# Amp_channel.net
KiCad netlist of a schematic drawn in Altium Designer
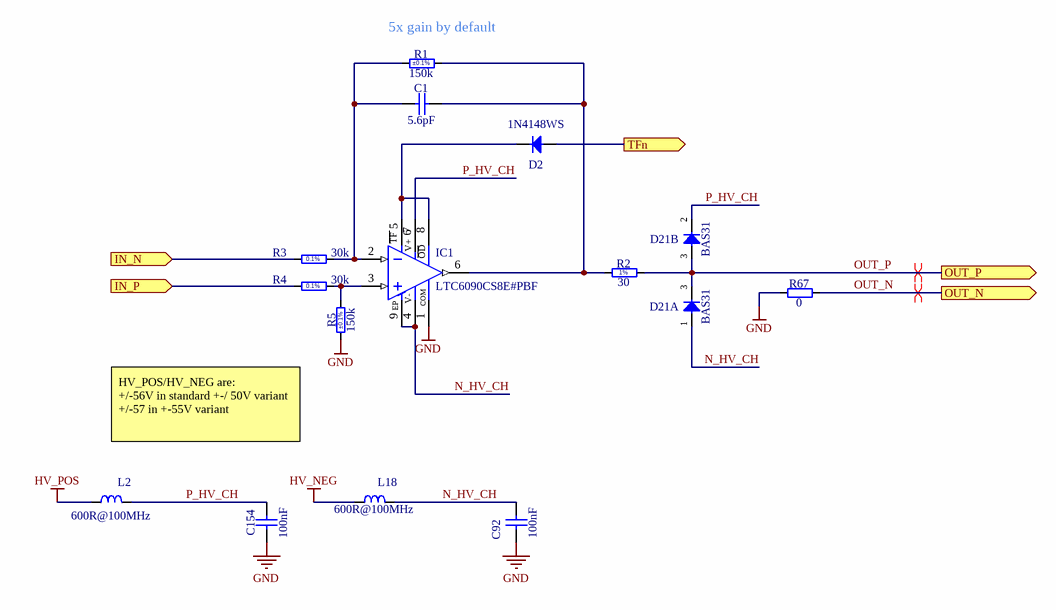
[diagram p0: Amp_channel.SchDoc]

(export (version "E")
  (design (tool "Eeschema 10.0.6"))
  (components
    (comp (ref "C1")
      (value "5.6pF")
      (footprint "CAPC1608X87N")
      (description "Non-polarised capacitor")
      (fields
        (field (name "PART NUMBER") "CC0603_5.6PF_50V_0.5PF_NP0")
        (field (name "MANUFACTURER") "GENERIC")
        (field (name "AUTHOR") "CERN DEM JLC")
      )
      (libsource (lib "Capacitors") (part "Capacitor - non polarized"))
    )
    (comp (ref "C92")
      (value "100nF")
      (footprint "CAPC1608X90N")
      (description "Non-polarised capacitor")
      (fields
        (field (name "PART NUMBER") "CC0603_100NF_100V_10%_X7R")
        (field (name "VOLTAGE") "100V")
        (field (name "AUTHOR") "CERN DEM JLC")
      )
      (libsource (lib "Capacitors") (part "Capacitor - non polarized"))
    )
    (comp (ref "C154")
      (value "100nF")
      (footprint "CAPC1608X90N")
      (description "Non-polarised capacitor")
      (fields
        (field (name "PART NUMBER") "CC0603_100NF_100V_10%_X7R")
        (field (name "VOLTAGE") "100V")
        (field (name "AUTHOR") "CERN DEM JLC")
      )
      (libsource (lib "Capacitors") (part "Capacitor - non polarized"))
    )
    (comp (ref "D2")
      (value "1N4148WS")
      (footprint "SODFL2512X100N")
      (description "Diode")
      (fields
        (field (name "VOLTAGE") "75V")
        (field (name "POWER") "150mA")
        (field (name "AUTHOR") "CERN DEM JLC")
      )
      (libsource (lib "ICs And Semiconductors") (part "Diode"))
    )
    (comp (ref "D21")
      (value "BAS31")
      (footprint "SOT95P240X130-3N")
      (description "Serial Diode")
      (fields
        (field (name "VOLTAGE") "120V")
        (field (name "POWER") "200mA")
        (field (name "AUTHOR") "CERN DEM JLC")
      )
      (libsource (lib "ICs And Semiconductors") (part "Diode x2 A1C3_A3C2"))
    )
    (comp (ref "IC1")
      (value "LTC6090CS8E#PBF")
      (footprint "SOIC127P599X175-9N-R249X350")
      (description "140V CMOS Rail-to-Rail Output, Picoamp Input Current Operational Amplifier")
      (fields (field (name "MANUFACTURER") "LINEAR TECHNOLOGY") (field (name "AUTHOR") "CERN DEM JLC"))
      (libsource (lib "ICs And Semiconductors") (part "LTC6090CS8E"))
    )
    (comp (ref "L2")
      (value "600R@100MHz")
      (footprint "INDC1005X55N")
      (description "Inductor")
      (fields
        (field (name "PART NUMBER") "IND0402_MURATA_BLM15HD601SN1")
        (field (name "POWER") "300mA")
        (field (name "AUTHOR") "CERN DEM JLC")
      )
      (libsource (lib "Inductors & Transformers") (part "Inductor"))
    )
    (comp (ref "L18")
      (value "600R@100MHz")
      (footprint "INDC1005X55N")
      (description "Inductor")
      (fields
        (field (name "PART NUMBER") "IND0402_MURATA_BLM15HD601SN1")
        (field (name "POWER") "300mA")
        (field (name "AUTHOR") "CERN DEM JLC")
      )
      (libsource (lib "Inductors & Transformers") (part "Inductor"))
    )
    (comp (ref "R1")
      (value "150k")
      (footprint "RESC1608X55N")
      (description "Resistor - 0.1%")
      (fields
        (field (name "TOLERANCE") "±0.1%")
        (field (name "PART NUMBER") "R0603_150K_0.1%_0.063W_10PPM")
        (field (name "POWER") "0.063W")
        (field (name "AUTHOR") "CERN DEM JLC")
      )
      (libsource (lib "Resistors") (part "Resistor - 0.1%"))
    )
    (comp (ref "R2")
      (value "30")
      (footprint "RESC1608X55N")
      (description "Resistor - 1%")
      (fields
        (field (name "PART NUMBER") "R0603_30R_1%_0.1W_100PPM")
        (field (name "POWER") "0.1W")
        (field (name "AUTHOR") "CERN DEM JLC")
      )
      (libsource (lib "Resistors") (part "Resistor - 1%"))
    )
    (comp (ref "R3")
      (value "30k")
      (footprint "RESC1005X40N")
      (description "Resistor - 1%")
      (fields
        (field (name "PART NUMBER") "R0603_30K0_0.1%_0.063W_10PPM")
        (field (name "POWER") "0.063W")
        (field (name "AUTHOR") "GK")
      )
      (libsource (lib "Passives_RC") (part "R0603_30K0_0.1%_0.063W_10PPM"))
    )
    (comp (ref "R4")
      (value "30k")
      (footprint "RESC1005X40N")
      (description "Resistor - 1%")
      (fields
        (field (name "PART NUMBER") "R0603_30K0_0.1%_0.063W_10PPM")
        (field (name "POWER") "0.063W")
        (field (name "AUTHOR") "GK")
      )
      (libsource (lib "Passives_RC") (part "R0603_30K0_0.1%_0.063W_10PPM"))
    )
    (comp (ref "R5")
      (value "150k")
      (footprint "RESC1608X55N")
      (description "Resistor - 0.1%")
      (fields
        (field (name "TOLERANCE") "±0.1%")
        (field (name "PART NUMBER") "R0603_150K_0.1%_0.063W_10PPM")
        (field (name "POWER") "0.063W")
        (field (name "AUTHOR") "CERN DEM JLC")
      )
      (libsource (lib "Resistors") (part "Resistor - 0.1%"))
    )
    (comp (ref "R67")
      (value "0")
      (footprint "RESC1608X55N")
      (description "Resistor")
      (fields
        (field (name "PART NUMBER") "R0603_0R_JUMPER")
        (field (name "MANUFACTURER") "GENERIC")
        (field (name "AUTHOR") "CERN DEM JLC")
      )
      (libsource (lib "Resistors") (part "Resistor"))
    )
  )
  (nets
    (net (code "1") (name "/IN_N") (class "Default")
      (node (ref "R3") (pin "1") (pinfunction "1_1") (pintype "passive"))
    )
    (net (code "2") (name "/IN_P") (class "Default")
      (node (ref "R4") (pin "1") (pinfunction "1_1") (pintype "passive"))
    )
    (net (code "3") (name "/N_HV_CH") (class "Default")
      (node (ref "C92") (pin "2") (pinfunction "2_2") (pintype "passive"))
      (node (ref "D21") (pin "1") (pinfunction "A_1") (pintype "passive"))
      (node (ref "IC1") (pin "4") (pinfunction "V-_4") (pintype "power_in"))
      (node (ref "IC1") (pin "9") (pinfunction "EP_9") (pintype "power_in"))
      (node (ref "L18") (pin "2") (pinfunction "2_2") (pintype "passive"))
    )
    (net (code "4") (name "/OUT_N") (class "Default")
      (node (ref "R67") (pin "2") (pinfunction "2_2") (pintype "passive"))
    )
    (net (code "5") (name "/OUT_P") (class "Default")
      (node (ref "D21") (pin "3") (pinfunction "COMAC_3") (pintype "passive"))
      (node (ref "R2") (pin "2") (pinfunction "2_2") (pintype "passive"))
    )
    (net (code "6") (name "/P_HV_CH") (class "Default")
      (node (ref "C154") (pin "2") (pinfunction "2_2") (pintype "passive"))
      (node (ref "D21") (pin "2") (pinfunction "C_2") (pintype "passive"))
      (node (ref "IC1") (pin "7") (pinfunction "V+_7") (pintype "power_in"))
      (node (ref "L2") (pin "2") (pinfunction "2_2") (pintype "passive"))
    )
    (net (code "7") (name "/TFn") (class "Default")
      (node (ref "D2") (pin "2") (pinfunction "A_2") (pintype "passive"))
    )
    (net (code "8") (name "GND") (class "Default")
      (node (ref "C154") (pin "1") (pinfunction "1_1") (pintype "passive"))
      (node (ref "C92") (pin "1") (pinfunction "1_1") (pintype "passive"))
      (node (ref "IC1") (pin "1") (pinfunction "COM_1") (pintype "power_in"))
      (node (ref "R5") (pin "1") (pinfunction "1_1") (pintype "passive"))
      (node (ref "R67") (pin "1") (pinfunction "1_1") (pintype "passive"))
    )
    (net (code "9") (name "HV_NEG") (class "Default")
      (node (ref "L18") (pin "1") (pinfunction "1_1") (pintype "passive"))
    )
    (net (code "10") (name "HV_POS") (class "Default")
      (node (ref "L2") (pin "1") (pinfunction "1_1") (pintype "passive"))
    )
    (net (code "11") (name "Net-(D2-C)") (class "Default")
      (node (ref "D2") (pin "1") (pinfunction "C_1") (pintype "passive"))
      (node (ref "IC1") (pin "5") (pinfunction "~{TFLAG}_5") (pintype "passive"))
      (node (ref "IC1") (pin "8") (pinfunction "~{OD}_8") (pintype "passive"))
    )
    (net (code "12") (name "Net-(IC1-IN+)") (class "Default")
      (node (ref "IC1") (pin "3") (pinfunction "IN+_3") (pintype "input"))
      (node (ref "R4") (pin "2") (pinfunction "2_2") (pintype "passive"))
      (node (ref "R5") (pin "2") (pinfunction "2_2") (pintype "passive"))
    )
    (net (code "13") (name "Net-(IC1-IN-)") (class "Default")
      (node (ref "C1") (pin "1") (pinfunction "1_1") (pintype "passive"))
      (node (ref "IC1") (pin "2") (pinfunction "IN-_2") (pintype "input"))
      (node (ref "R1") (pin "1") (pinfunction "1_1") (pintype "passive"))
      (node (ref "R3") (pin "2") (pinfunction "2_2") (pintype "passive"))
    )
    (net (code "14") (name "Net-(IC1-OUT)") (class "Default")
      (node (ref "C1") (pin "2") (pinfunction "2_2") (pintype "passive"))
      (node (ref "IC1") (pin "6") (pinfunction "OUT_6") (pintype "output"))
      (node (ref "R1") (pin "2") (pinfunction "2_2") (pintype "passive"))
      (node (ref "R2") (pin "1") (pinfunction "1_1") (pintype "passive"))
    )
    (net (code "15") (name "unconnected-(IC1-~{TFLAG}-Pad6)") (class "Default")
      (node (ref "IC1") (pin "6") (pinfunction "~{TFLAG}_6") (pintype "passive"))
    )
  )
)
